# dcf77kompZDiff.net
KiCad netlist of a schematic drawn in EAGLE
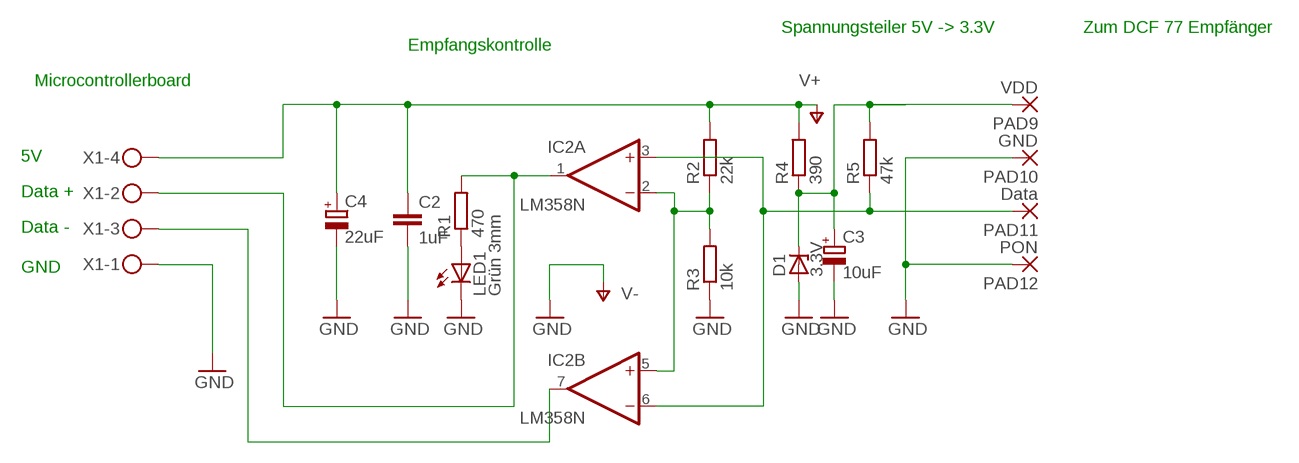
[diagram p0: schematic, sheet 1]

(export (version "E")
  (design (tool "Eeschema 10.0.6"))
  (components
    (comp (ref "C2")
      (value "1uF")
      (footprint "eagle-import:C050-050X075")
      (libsource (lib "eagle-import") (part "C-EU050-050X075"))
    )
    (comp (ref "C3")
      (value "10uF")
      (footprint "eagle-import:E2,5-5")
      (libsource (lib "eagle-import") (part "CPOL-EUE2.5-5"))
    )
    (comp (ref "C4")
      (value "22uF")
      (footprint "eagle-import:E5-10,5")
      (libsource (lib "eagle-import") (part "resistor_CPOL-EUE5-10.5"))
    )
    (comp (ref "D1")
      (value "3.3V")
      (footprint "eagle-import:DO34Z7")
      (libsource (lib "eagle-import") (part "ZENER-DIODEDO34-7"))
    )
    (comp (ref "IC2")
      (value "LM358N")
      (footprint "eagle-import:DIL08")
      (libsource (lib "eagle-import") (part "LM358N"))
    )
    (comp (ref "LED1")
      (value "Grün 3mm")
      (footprint "eagle-import:LED5MM")
      (libsource (lib "eagle-import") (part "LED5MM"))
    )
    (comp (ref "PAD9")
      (value "VDD")
      (footprint "eagle-import:1,6_0,9")
      (libsource (lib "eagle-import") (part "1,6/0,9"))
    )
    (comp (ref "PAD10")
      (value "GND")
      (footprint "eagle-import:1,6_0,9")
      (libsource (lib "eagle-import") (part "1,6/0,9"))
    )
    (comp (ref "PAD11")
      (value "Data")
      (footprint "eagle-import:1,6_0,9")
      (libsource (lib "eagle-import") (part "1,6/0,9"))
    )
    (comp (ref "PAD12")
      (value "PON")
      (footprint "eagle-import:1,6_0,9")
      (libsource (lib "eagle-import") (part "1,6/0,9"))
    )
    (comp (ref "R1")
      (value "470")
      (footprint "eagle-import:0207_10")
      (libsource (lib "eagle-import") (part "R-EU_0207/10"))
    )
    (comp (ref "R2")
      (value "22k")
      (footprint "eagle-import:0207_10")
      (libsource (lib "eagle-import") (part "R-EU_0207/10"))
    )
    (comp (ref "R3")
      (value "10k")
      (footprint "eagle-import:0207_10")
      (libsource (lib "eagle-import") (part "R-EU_0207/10"))
    )
    (comp (ref "R4")
      (value "390")
      (footprint "eagle-import:0207_10")
      (libsource (lib "eagle-import") (part "R-EU_0207/10"))
    )
    (comp (ref "R5")
      (value "47k")
      (footprint "eagle-import:0207_10")
      (libsource (lib "eagle-import") (part "R-EU_0207/10"))
    )
    (comp (ref "X1")
      (value "MKDSN1,5/4-5,08")
      (footprint "eagle-import:MKDSN1,5_4-5,08")
      (fields (field (name "MPN") "SMKDSN1,5/4-5,08"))
      (libsource (lib "eagle-import") (part "MKDSN1,5/4-5,08"))
    )
  )
  (nets
    (net (code "1") (name "GND") (class "Default")
      (node (ref "C2") (pin "2") (pinfunction "2_2") (pintype "passive"))
      (node (ref "C3") (pin "-") (pinfunction "-_-") (pintype "passive"))
      (node (ref "C4") (pin "-") (pinfunction "-_-") (pintype "passive"))
      (node (ref "D1") (pin "A") (pinfunction "A_A") (pintype "passive"))
      (node (ref "LED1") (pin "K") (pinfunction "C_K") (pintype "passive"))
      (node (ref "PAD10") (pin "1") (pinfunction "P_1") (pintype "passive"))
      (node (ref "PAD12") (pin "1") (pinfunction "P_1") (pintype "passive"))
      (node (ref "R3") (pin "1") (pinfunction "1_1") (pintype "passive"))
      (node (ref "X1") (pin "1") (pinfunction "KL_1") (pintype "passive"))
    )
    (net (code "2") (name "Net-(IC2A-+IN)") (class "Default")
      (node (ref "IC2") (pin "3") (pinfunction "+IN_3") (pintype "input"))
      (node (ref "IC2") (pin "6") (pinfunction "-IN_6") (pintype "input"))
      (node (ref "PAD11") (pin "1") (pinfunction "P_1") (pintype "passive"))
      (node (ref "R5") (pin "1") (pinfunction "1_1") (pintype "passive"))
    )
    (net (code "3") (name "Net-(IC2A--IN)") (class "Default")
      (node (ref "IC2") (pin "2") (pinfunction "-IN_2") (pintype "input"))
      (node (ref "IC2") (pin "5") (pinfunction "+IN_5") (pintype "input"))
      (node (ref "R2") (pin "1") (pinfunction "1_1") (pintype "passive"))
      (node (ref "R3") (pin "2") (pinfunction "2_2") (pintype "passive"))
    )
    (net (code "4") (name "Net-(IC2A-OUT)") (class "Default")
      (node (ref "IC2") (pin "1") (pinfunction "OUT_1") (pintype "output"))
      (node (ref "R1") (pin "2") (pinfunction "2_2") (pintype "passive"))
      (node (ref "X1") (pin "2") (pinfunction "KL_2") (pintype "passive"))
    )
    (net (code "5") (name "Net-(IC2B-OUT)") (class "Default")
      (node (ref "IC2") (pin "7") (pinfunction "OUT_7") (pintype "output"))
      (node (ref "X1") (pin "3") (pinfunction "KL_3") (pintype "passive"))
    )
    (net (code "6") (name "Net-(LED1-PadA)") (class "Default")
      (node (ref "LED1") (pin "A") (pinfunction "A_A") (pintype "passive"))
      (node (ref "R1") (pin "1") (pinfunction "1_1") (pintype "passive"))
    )
    (net (code "7") (name "Net-(PAD9-P)") (class "Default")
      (node (ref "C3") (pin "+") (pinfunction "+_+") (pintype "passive"))
      (node (ref "D1") (pin "C") (pinfunction "C_C") (pintype "passive"))
      (node (ref "PAD9") (pin "1") (pinfunction "P_1") (pintype "passive"))
      (node (ref "R4") (pin "1") (pinfunction "1_1") (pintype "passive"))
      (node (ref "R5") (pin "2") (pinfunction "2_2") (pintype "passive"))
    )
    (net (code "8") (name "V+") (class "Default")
      (node (ref "C2") (pin "1") (pinfunction "1_1") (pintype "passive"))
      (node (ref "C4") (pin "+") (pinfunction "+_+") (pintype "passive"))
      (node (ref "R2") (pin "2") (pinfunction "2_2") (pintype "passive"))
      (node (ref "R4") (pin "2") (pinfunction "2_2") (pintype "passive"))
      (node (ref "X1") (pin "4") (pinfunction "KL_4") (pintype "passive"))
    )
  )
)
